# ESP-01s_board_to_PZEM-004.net
KiCad netlist of a schematic drawn in EasyEDA
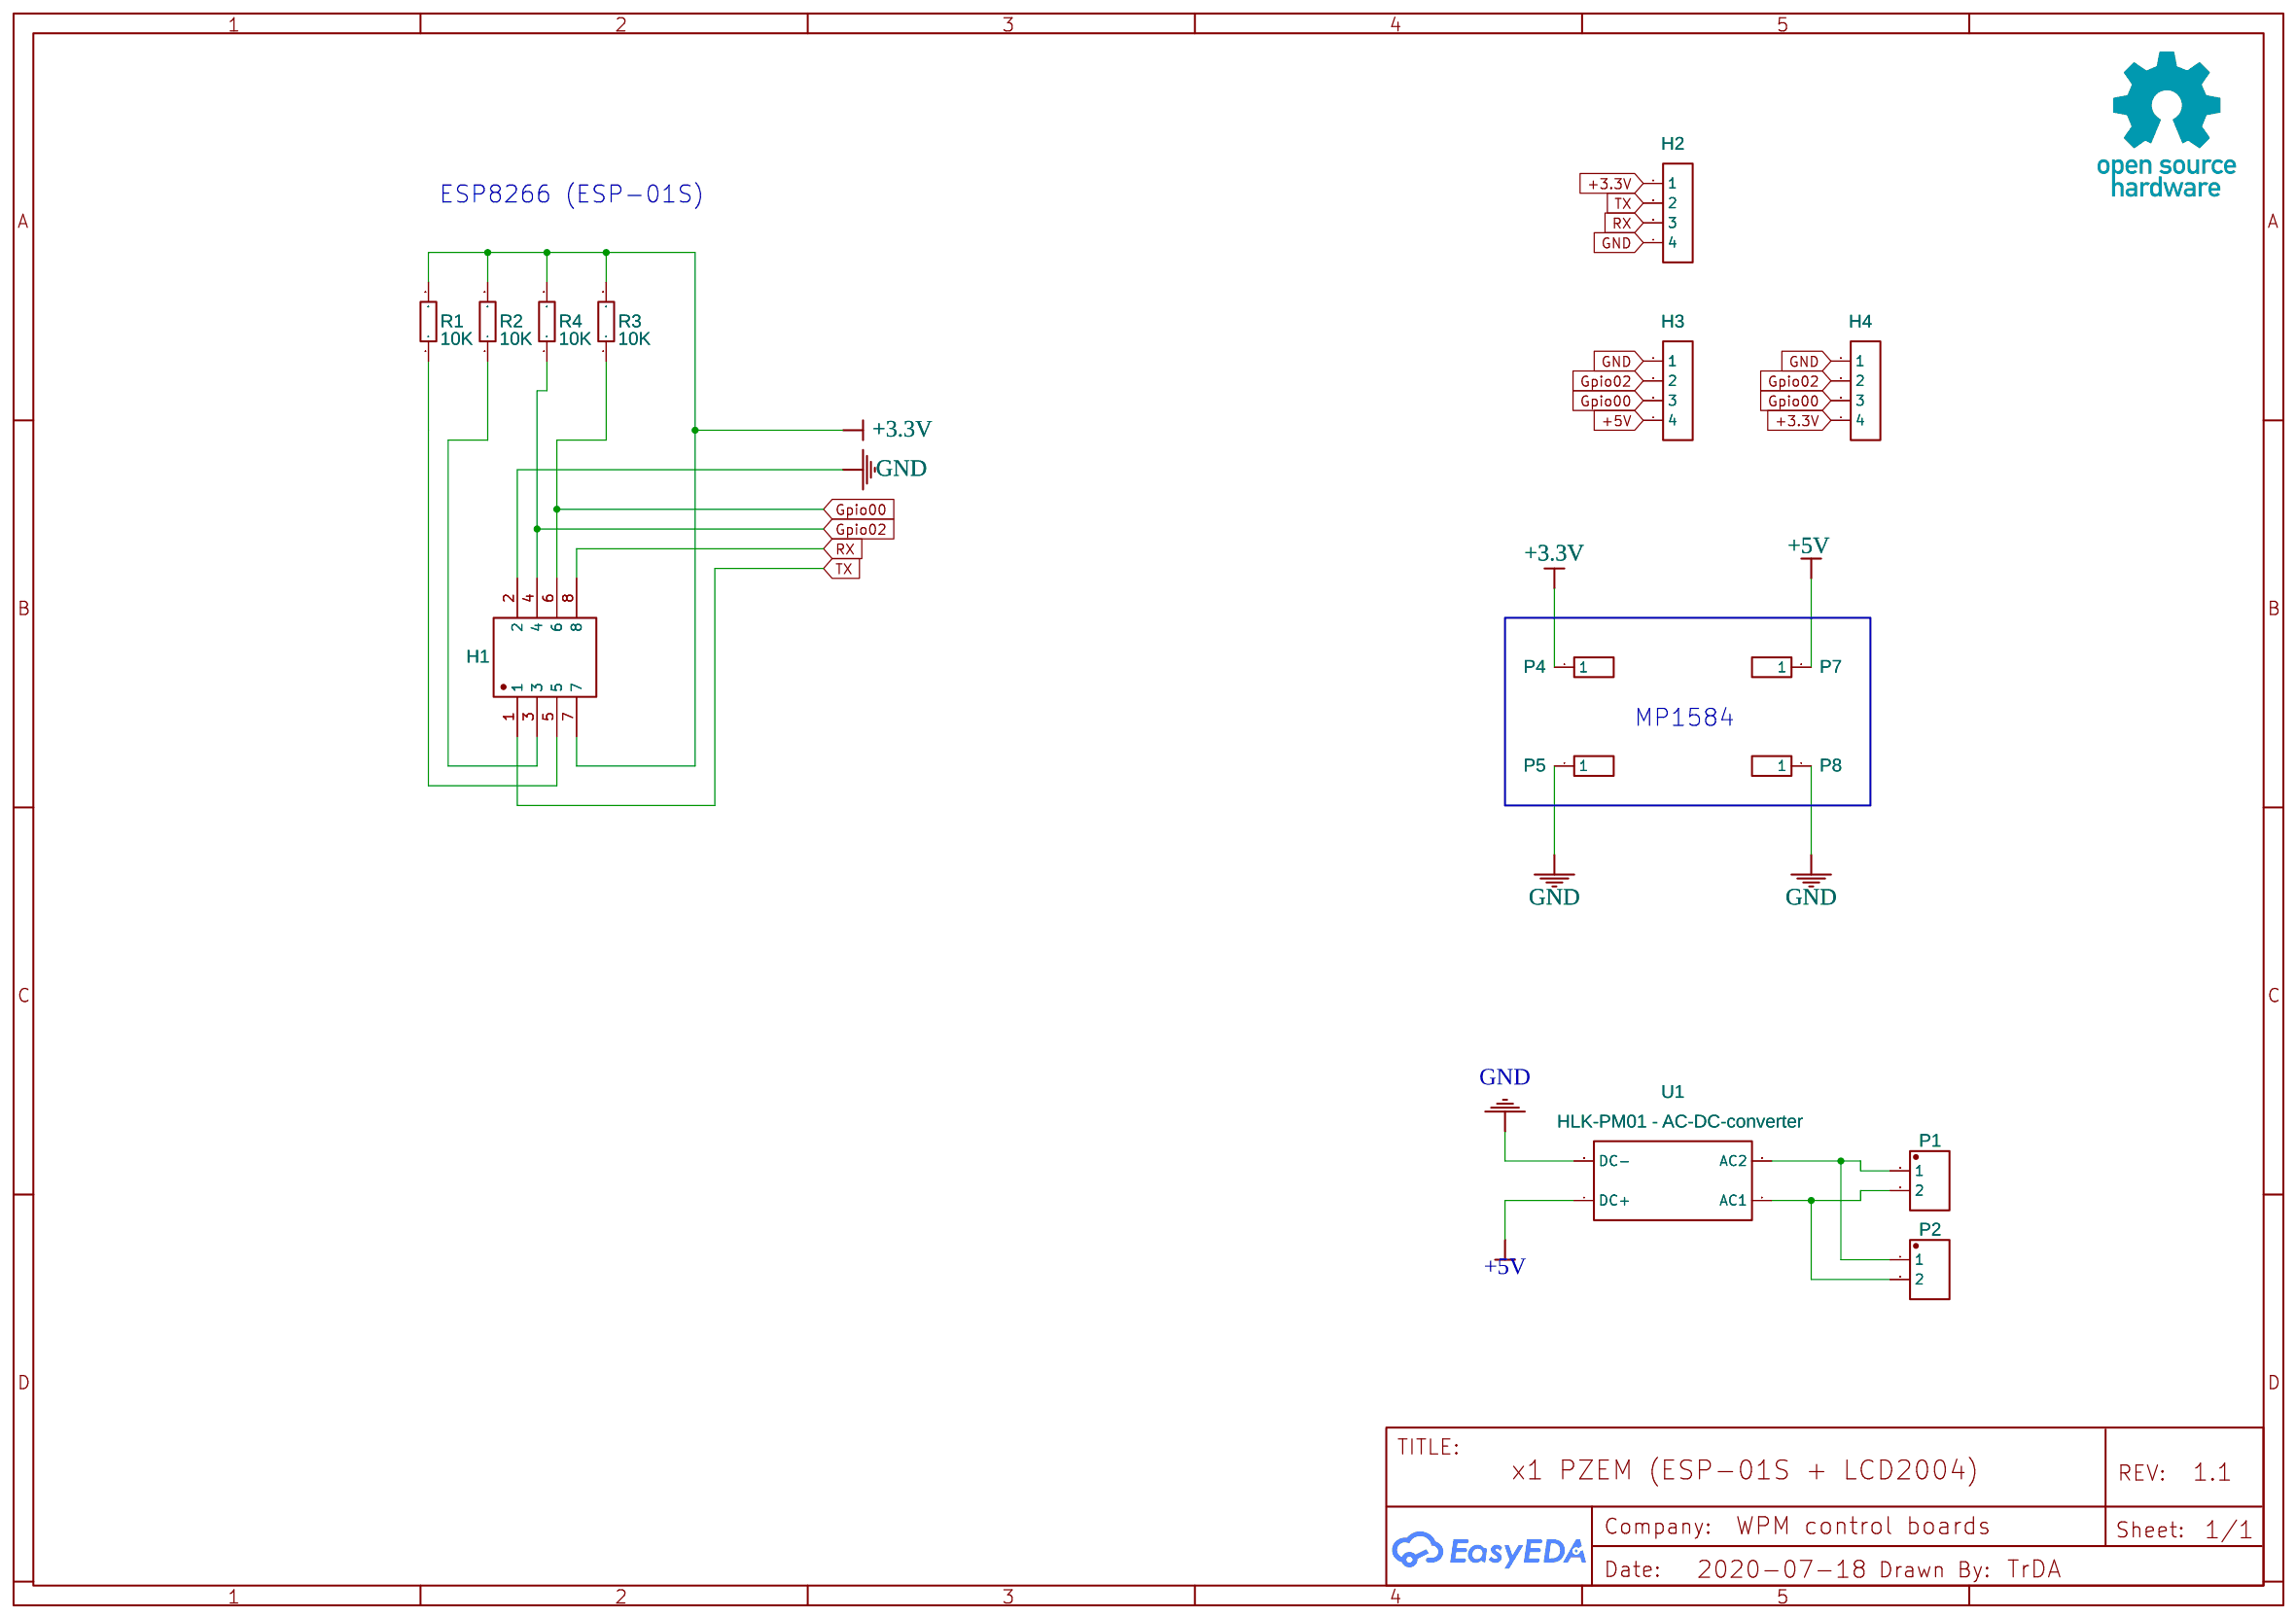
[diagram p0: schematic sheet]

(export (version "E")
  (design (tool "Eeschema 10.0.6"))
  (components
    (comp (ref "H1")
      (value "210S-2*4P L=11.6MMGold-plated black")
      (fields (field (name "BOM_Supplier Part") "C124386"))
      (libsource (lib "") (part "210S-2*4P L=11.6MMGold-plated black"))
    )
    (comp (ref "H2")
      (value "B4B-XH-AM_(LF)(SN)")
      (fields (field (name "BOM_Supplier Part") "C161872"))
      (libsource (lib "") (part "B4B-XH-AM_(LF)(SN)"))
    )
    (comp (ref "H3")
      (value "B4B-XH-AM_(LF)(SN)")
      (fields (field (name "BOM_Supplier Part") "C161872"))
      (libsource (lib "") (part "B4B-XH-AM_(LF)(SN)"))
    )
    (comp (ref "H4")
      (value "B4B-XH-AM_(LF)(SN)")
      (fields (field (name "BOM_Supplier Part") "C161872"))
      (libsource (lib "") (part "B4B-XH-AM_(LF)(SN)"))
    )
    (comp (ref "P1")
      (value "WJ2EDGVC-5.08-2P")
      (fields (field (name "BOM_Supplier Part") "C8445"))
      (libsource (lib "") (part "WJ2EDGVC-5.08-2P"))
    )
    (comp (ref "P2")
      (value "WJ2EDGVC-5.08-2P")
      (fields (field (name "BOM_Supplier Part") "C8445"))
      (libsource (lib "") (part "WJ2EDGVC-5.08-2P"))
    )
    (comp (ref "P4")
      (value "Header-Male-2.54_1x1")
      (fields (field (name "BOM_Supplier Part") "C81276"))
      (libsource (lib "") (part "Header-Male-2.54_1x1"))
    )
    (comp (ref "P5")
      (value "Header-Male-2.54_1x1")
      (fields (field (name "BOM_Supplier Part") "C81276"))
      (libsource (lib "") (part "Header-Male-2.54_1x1"))
    )
    (comp (ref "P7")
      (value "Header-Male-2.54_1x1")
      (fields (field (name "BOM_Supplier Part") "C81276"))
      (libsource (lib "") (part "Header-Male-2.54_1x1_1"))
    )
    (comp (ref "P8")
      (value "Header-Male-2.54_1x1")
      (fields (field (name "BOM_Supplier Part") "C81276"))
      (libsource (lib "") (part "Header-Male-2.54_1x1_1"))
    )
    (comp (ref "R1")
      (value "10K")
      (fields
        (field (name "BOM_Manufacturer Part") "RT0805DRD0710KL")
        (field (name "BOM_Supplier Part") "C165963")
      )
      (libsource (lib "") (part "RT0805DRD0710KL"))
    )
    (comp (ref "R2")
      (value "10K")
      (fields
        (field (name "BOM_Manufacturer Part") "RT0805DRD0710KL")
        (field (name "BOM_Supplier Part") "C165963")
      )
      (libsource (lib "") (part "RT0805DRD0710KL"))
    )
    (comp (ref "R3")
      (value "10K")
      (fields
        (field (name "BOM_Manufacturer Part") "RT0805DRD0710KL")
        (field (name "BOM_Supplier Part") "C165963")
      )
      (libsource (lib "") (part "RT0805DRD0710KL"))
    )
    (comp (ref "R4")
      (value "10K")
      (fields
        (field (name "BOM_Manufacturer Part") "RT0805DRD0710KL")
        (field (name "BOM_Supplier Part") "C165963")
      )
      (libsource (lib "") (part "RT0805DRD0710KL"))
    )
    (comp (ref "U1")
      (value "HLK-PM01 - AC-DC-converter")
      (libsource (lib "") (part "HLK-PM01 - AC-DC-converter"))
    )
  )
  (nets
    (net (code "1") (name "+3.3V") (class "Default")
      (node (ref "H1") (pin "7") (pinfunction "7_7") (pintype "unspecified"))
      (node (ref "H2") (pin "1") (pinfunction "1_1") (pintype "unspecified"))
      (node (ref "H4") (pin "4") (pinfunction "4_4") (pintype "unspecified"))
      (node (ref "P4") (pin "1") (pinfunction "1_1") (pintype "input"))
      (node (ref "R1") (pin "2") (pinfunction "2_2") (pintype "unspecified"))
      (node (ref "R2") (pin "2") (pinfunction "2_2") (pintype "unspecified"))
      (node (ref "R3") (pin "2") (pinfunction "2_2") (pintype "unspecified"))
      (node (ref "R4") (pin "2") (pinfunction "2_2") (pintype "unspecified"))
    )
    (net (code "2") (name "+5V") (class "Default")
      (node (ref "H3") (pin "4") (pinfunction "4_4") (pintype "unspecified"))
      (node (ref "P7") (pin "1") (pinfunction "1_1") (pintype "input"))
      (node (ref "U1") (pin "4") (pinfunction "DC+_4") (pintype "unspecified"))
    )
    (net (code "3") (name "GND") (class "Default")
      (node (ref "H1") (pin "2") (pinfunction "2_2") (pintype "unspecified"))
      (node (ref "H2") (pin "4") (pinfunction "4_4") (pintype "unspecified"))
      (node (ref "H3") (pin "1") (pinfunction "1_1") (pintype "unspecified"))
      (node (ref "H4") (pin "1") (pinfunction "1_1") (pintype "unspecified"))
      (node (ref "P5") (pin "1") (pinfunction "1_1") (pintype "input"))
      (node (ref "P8") (pin "1") (pinfunction "1_1") (pintype "input"))
      (node (ref "U1") (pin "3") (pinfunction "DC-_3") (pintype "unspecified"))
    )
    (net (code "4") (name "Gpio00") (class "Default")
      (node (ref "H1") (pin "6") (pinfunction "6_6") (pintype "unspecified"))
      (node (ref "H3") (pin "3") (pinfunction "3_3") (pintype "unspecified"))
      (node (ref "H4") (pin "3") (pinfunction "3_3") (pintype "unspecified"))
      (node (ref "R3") (pin "1") (pinfunction "1_1") (pintype "unspecified"))
    )
    (net (code "5") (name "Gpio02") (class "Default")
      (node (ref "H1") (pin "4") (pinfunction "4_4") (pintype "unspecified"))
      (node (ref "H3") (pin "2") (pinfunction "2_2") (pintype "unspecified"))
      (node (ref "H4") (pin "2") (pinfunction "2_2") (pintype "unspecified"))
      (node (ref "R4") (pin "1") (pinfunction "1_1") (pintype "unspecified"))
    )
    (net (code "6") (name "Net-(H1-Pad3)") (class "Default")
      (node (ref "H1") (pin "3") (pinfunction "3_3") (pintype "unspecified"))
      (node (ref "R2") (pin "1") (pinfunction "1_1") (pintype "unspecified"))
    )
    (net (code "7") (name "Net-(H1-Pad5)") (class "Default")
      (node (ref "H1") (pin "5") (pinfunction "5_5") (pintype "unspecified"))
      (node (ref "R1") (pin "1") (pinfunction "1_1") (pintype "unspecified"))
    )
    (net (code "8") (name "Net-(U1-AC1)") (class "Default")
      (node (ref "P1") (pin "2") (pinfunction "2_2") (pintype "unspecified"))
      (node (ref "P2") (pin "2") (pinfunction "2_2") (pintype "unspecified"))
      (node (ref "U1") (pin "1") (pinfunction "AC1_1") (pintype "unspecified"))
    )
    (net (code "9") (name "Net-(U1-AC2)") (class "Default")
      (node (ref "P1") (pin "1") (pinfunction "1_1") (pintype "unspecified"))
      (node (ref "P2") (pin "1") (pinfunction "1_1") (pintype "unspecified"))
      (node (ref "U1") (pin "2") (pinfunction "AC2_2") (pintype "unspecified"))
    )
    (net (code "10") (name "RX") (class "Default")
      (node (ref "H1") (pin "8") (pinfunction "8_8") (pintype "unspecified"))
      (node (ref "H2") (pin "3") (pinfunction "3_3") (pintype "unspecified"))
    )
    (net (code "11") (name "TX") (class "Default")
      (node (ref "H1") (pin "1") (pinfunction "1_1") (pintype "unspecified"))
      (node (ref "H2") (pin "2") (pinfunction "2_2") (pintype "unspecified"))
    )
  )
)
